# sch.net
KiCad netlist of a schematic drawn in EAGLE
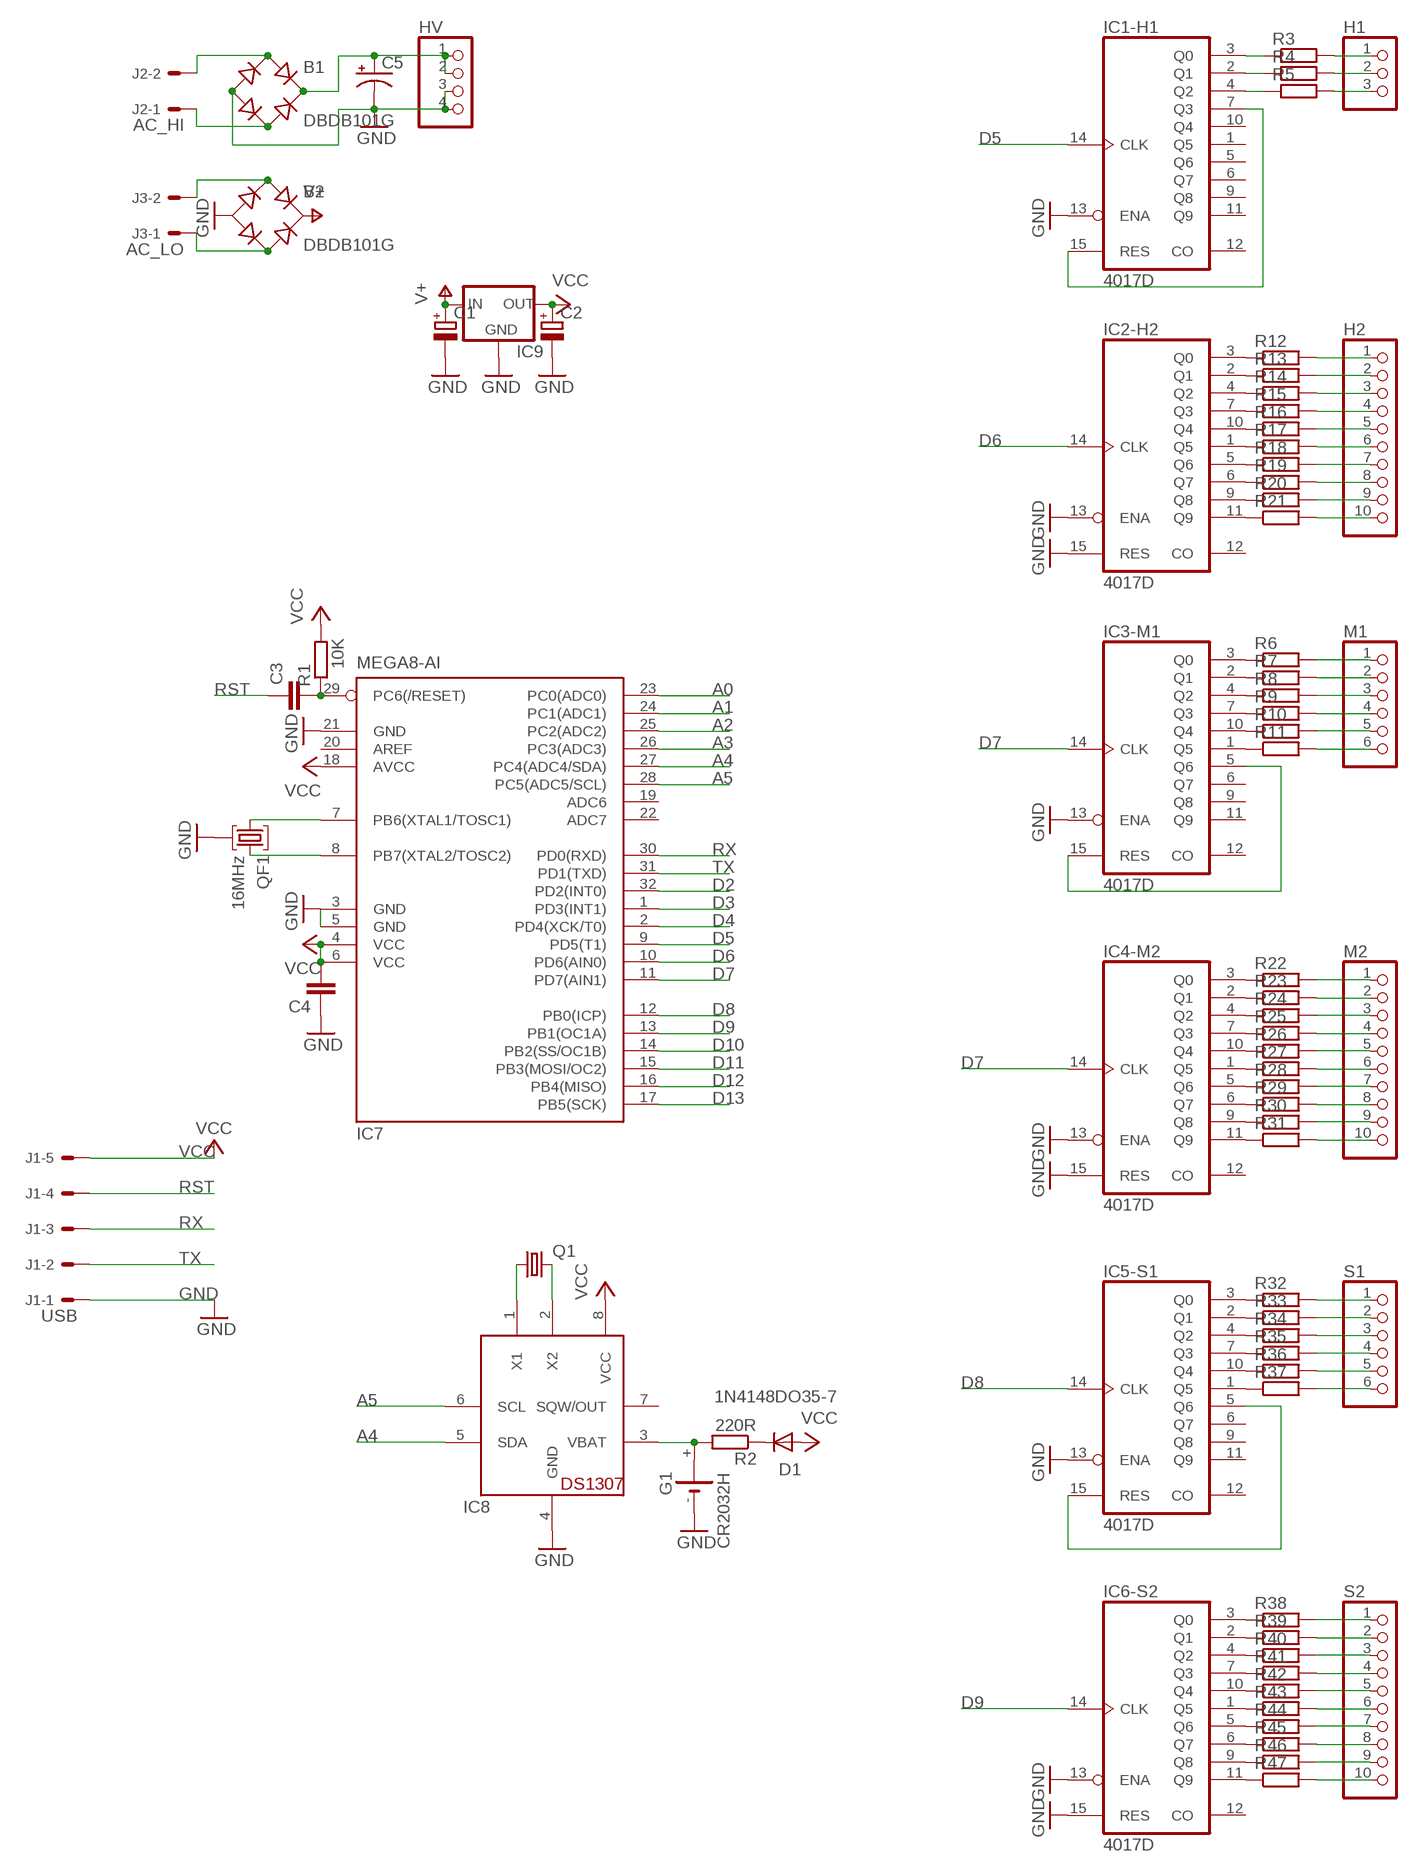
[diagram p0: schematic, sheet 1]

(export (version "E")
  (design (tool "Eeschema 10.0.6"))
  (components
    (comp (ref "B1")
      (value "DBDB101G")
      (footprint "eagle-import:DB")
      (libsource (lib "eagle-import") (part "DB?GDB101"))
    )
    (comp (ref "B2")
      (value "DBDB101G")
      (footprint "eagle-import:DB")
      (libsource (lib "eagle-import") (part "DB?GDB101"))
    )
    (comp (ref "C1")
      (value "CPOL-EU140CLH-1010")
      (footprint "eagle-import:140CLH-1010")
      (libsource (lib "eagle-import") (part "CPOL-EU140CLH-1010"))
    )
    (comp (ref "C2")
      (value "CPOL-EU140CLH-1010")
      (footprint "eagle-import:140CLH-1010")
      (libsource (lib "eagle-import") (part "CPOL-EU140CLH-1010"))
    )
    (comp (ref "C3")
      (value "C-EUC1206K")
      (footprint "eagle-import:C1206K")
      (libsource (lib "eagle-import") (part "C-EUC1206K"))
    )
    (comp (ref "C4")
      (value "C-EUC1206K")
      (footprint "eagle-import:C1206K")
      (libsource (lib "eagle-import") (part "C-EUC1206K"))
    )
    (comp (ref "C5")
      (value "CPOL-USE5-13")
      (footprint "eagle-import:E5-13")
      (libsource (lib "eagle-import") (part "CPOL-USE5-13"))
    )
    (comp (ref "D1")
      (value "1N4148DO35-7")
      (footprint "eagle-import:DO35-7")
      (libsource (lib "eagle-import") (part "1N4148DO35-7"))
    )
    (comp (ref "G1")
      (value "CR2032H")
      (footprint "eagle-import:CR2032H")
      (libsource (lib "eagle-import") (part "CR2032H"))
    )
    (comp (ref "H1")
      (value "PINHD-1X3")
      (footprint "eagle-import:1X03")
      (libsource (lib "eagle-import") (part "PINHD-1X3"))
    )
    (comp (ref "H2")
      (value "PINHD-1X10")
      (footprint "eagle-import:1X10")
      (libsource (lib "eagle-import") (part "PINHD-1X10"))
    )
    (comp (ref "HV")
      (value "PINHD-1X4")
      (footprint "eagle-import:1X04")
      (libsource (lib "eagle-import") (part "PINHD-1X4"))
    )
    (comp (ref "IC1-H1")
      (value "4017D")
      (footprint "eagle-import:SO16")
      (libsource (lib "eagle-import") (part "4017D"))
    )
    (comp (ref "IC2-H2")
      (value "4017D")
      (footprint "eagle-import:SO16")
      (libsource (lib "eagle-import") (part "4017D"))
    )
    (comp (ref "IC3-M1")
      (value "4017D")
      (footprint "eagle-import:SO16")
      (libsource (lib "eagle-import") (part "4017D"))
    )
    (comp (ref "IC4-M2")
      (value "4017D")
      (footprint "eagle-import:SO16")
      (libsource (lib "eagle-import") (part "4017D"))
    )
    (comp (ref "IC5-S1")
      (value "4017D")
      (footprint "eagle-import:SO16")
      (libsource (lib "eagle-import") (part "4017D"))
    )
    (comp (ref "IC6-S2")
      (value "4017D")
      (footprint "eagle-import:SO16")
      (libsource (lib "eagle-import") (part "4017D"))
    )
    (comp (ref "IC7")
      (value "MEGA8-AI")
      (footprint "eagle-import:TQFP32-08")
      (fields (field (name "MPN") "ATMEGA8-16AU"))
      (libsource (lib "eagle-import") (part "MEGA8-AI"))
    )
    (comp (ref "IC8")
      (value "DS1307")
      (footprint "eagle-import:DIL08")
      (libsource (lib "eagle-import") (part "DS1307"))
    )
    (comp (ref "IC9")
      (value "78XXS")
      (footprint "eagle-import:78XXS")
      (libsource (lib "eagle-import") (part "78XXS"))
    )
    (comp (ref "J1")
      (value "USB")
      (footprint "eagle-import:7395-05")
      (libsource (lib "eagle-import") (part "22-?-0505-7058"))
    )
    (comp (ref "J2")
      (value "AC_HI")
      (footprint "eagle-import:7395-02")
      (libsource (lib "eagle-import") (part "22-?-0205-7028"))
    )
    (comp (ref "J3")
      (value "AC_LO")
      (footprint "eagle-import:7395-02")
      (libsource (lib "eagle-import") (part "22-?-0205-7028"))
    )
    (comp (ref "M1")
      (value "PINHD-1X6")
      (footprint "eagle-import:1X06")
      (libsource (lib "eagle-import") (part "PINHD-1X6"))
    )
    (comp (ref "M2")
      (value "PINHD-1X10")
      (footprint "eagle-import:1X10")
      (libsource (lib "eagle-import") (part "PINHD-1X10"))
    )
    (comp (ref "Q1")
      (value "CRYSTALTC26H")
      (footprint "eagle-import:TC26H")
      (libsource (lib "eagle-import") (part "CRYSTALTC26H"))
    )
    (comp (ref "QF1")
      (value "16MHz")
      (footprint "eagle-import:HC49U")
      (libsource (lib "eagle-import") (part "8M10AHC49T"))
    )
    (comp (ref "R1")
      (value "10K")
      (footprint "eagle-import:0207_7")
      (libsource (lib "eagle-import") (part "R-EU_0207/7"))
    )
    (comp (ref "R2")
      (value "220R")
      (footprint "eagle-import:0207_7")
      (libsource (lib "eagle-import") (part "R-EU_0207/7"))
    )
    (comp (ref "R3")
      (value "R-EU_0204/5")
      (footprint "eagle-import:0204_5")
      (libsource (lib "eagle-import") (part "R-EU_0204/5"))
    )
    (comp (ref "R4")
      (value "R-EU_0204/5")
      (footprint "eagle-import:0204_5")
      (libsource (lib "eagle-import") (part "R-EU_0204/5"))
    )
    (comp (ref "R5")
      (value "R-EU_0204/5")
      (footprint "eagle-import:0204_5")
      (libsource (lib "eagle-import") (part "R-EU_0204/5"))
    )
    (comp (ref "R6")
      (value "R-EU_0204/5")
      (footprint "eagle-import:0204_5")
      (libsource (lib "eagle-import") (part "R-EU_0204/5"))
    )
    (comp (ref "R7")
      (value "R-EU_0204/5")
      (footprint "eagle-import:0204_5")
      (libsource (lib "eagle-import") (part "R-EU_0204/5"))
    )
    (comp (ref "R8")
      (value "R-EU_0204/5")
      (footprint "eagle-import:0204_5")
      (libsource (lib "eagle-import") (part "R-EU_0204/5"))
    )
    (comp (ref "R9")
      (value "R-EU_0204/5")
      (footprint "eagle-import:0204_5")
      (libsource (lib "eagle-import") (part "R-EU_0204/5"))
    )
    (comp (ref "R10")
      (value "R-EU_0204/5")
      (footprint "eagle-import:0204_5")
      (libsource (lib "eagle-import") (part "R-EU_0204/5"))
    )
    (comp (ref "R11")
      (value "R-EU_0204/5")
      (footprint "eagle-import:0204_5")
      (libsource (lib "eagle-import") (part "R-EU_0204/5"))
    )
    (comp (ref "R12")
      (value "R-EU_0204/5")
      (footprint "eagle-import:0204_5")
      (libsource (lib "eagle-import") (part "R-EU_0204/5"))
    )
    (comp (ref "R13")
      (value "R-EU_0204/5")
      (footprint "eagle-import:0204_5")
      (libsource (lib "eagle-import") (part "R-EU_0204/5"))
    )
    (comp (ref "R14")
      (value "R-EU_0204/5")
      (footprint "eagle-import:0204_5")
      (libsource (lib "eagle-import") (part "R-EU_0204/5"))
    )
    (comp (ref "R15")
      (value "R-EU_0204/5")
      (footprint "eagle-import:0204_5")
      (libsource (lib "eagle-import") (part "R-EU_0204/5"))
    )
    (comp (ref "R16")
      (value "R-EU_0204/5")
      (footprint "eagle-import:0204_5")
      (libsource (lib "eagle-import") (part "R-EU_0204/5"))
    )
    (comp (ref "R17")
      (value "R-EU_0204/5")
      (footprint "eagle-import:0204_5")
      (libsource (lib "eagle-import") (part "R-EU_0204/5"))
    )
    (comp (ref "R18")
      (value "R-EU_0204/5")
      (footprint "eagle-import:0204_5")
      (libsource (lib "eagle-import") (part "R-EU_0204/5"))
    )
    (comp (ref "R19")
      (value "R-EU_0204/5")
      (footprint "eagle-import:0204_5")
      (libsource (lib "eagle-import") (part "R-EU_0204/5"))
    )
    (comp (ref "R20")
      (value "R-EU_0204/5")
      (footprint "eagle-import:0204_5")
      (libsource (lib "eagle-import") (part "R-EU_0204/5"))
    )
    (comp (ref "R21")
      (value "R-EU_0204/5")
      (footprint "eagle-import:0204_5")
      (libsource (lib "eagle-import") (part "R-EU_0204/5"))
    )
    (comp (ref "R22")
      (value "R-EU_0204/5")
      (footprint "eagle-import:0204_5")
      (libsource (lib "eagle-import") (part "R-EU_0204/5"))
    )
    (comp (ref "R23")
      (value "R-EU_0204/5")
      (footprint "eagle-import:0204_5")
      (libsource (lib "eagle-import") (part "R-EU_0204/5"))
    )
    (comp (ref "R24")
      (value "R-EU_0204/5")
      (footprint "eagle-import:0204_5")
      (libsource (lib "eagle-import") (part "R-EU_0204/5"))
    )
    (comp (ref "R25")
      (value "R-EU_0204/5")
      (footprint "eagle-import:0204_5")
      (libsource (lib "eagle-import") (part "R-EU_0204/5"))
    )
    (comp (ref "R26")
      (value "R-EU_0204/5")
      (footprint "eagle-import:0204_5")
      (libsource (lib "eagle-import") (part "R-EU_0204/5"))
    )
    (comp (ref "R27")
      (value "R-EU_0204/5")
      (footprint "eagle-import:0204_5")
      (libsource (lib "eagle-import") (part "R-EU_0204/5"))
    )
    (comp (ref "R28")
      (value "R-EU_0204/5")
      (footprint "eagle-import:0204_5")
      (libsource (lib "eagle-import") (part "R-EU_0204/5"))
    )
    (comp (ref "R29")
      (value "R-EU_0204/5")
      (footprint "eagle-import:0204_5")
      (libsource (lib "eagle-import") (part "R-EU_0204/5"))
    )
    (comp (ref "R30")
      (value "R-EU_0204/5")
      (footprint "eagle-import:0204_5")
      (libsource (lib "eagle-import") (part "R-EU_0204/5"))
    )
    (comp (ref "R31")
      (value "R-EU_0204/5")
      (footprint "eagle-import:0204_5")
      (libsource (lib "eagle-import") (part "R-EU_0204/5"))
    )
    (comp (ref "R32")
      (value "R-EU_0204/5")
      (footprint "eagle-import:0204_5")
      (libsource (lib "eagle-import") (part "R-EU_0204/5"))
    )
    (comp (ref "R33")
      (value "R-EU_0204/5")
      (footprint "eagle-import:0204_5")
      (libsource (lib "eagle-import") (part "R-EU_0204/5"))
    )
    (comp (ref "R34")
      (value "R-EU_0204/5")
      (footprint "eagle-import:0204_5")
      (libsource (lib "eagle-import") (part "R-EU_0204/5"))
    )
    (comp (ref "R35")
      (value "R-EU_0204/5")
      (footprint "eagle-import:0204_5")
      (libsource (lib "eagle-import") (part "R-EU_0204/5"))
    )
    (comp (ref "R36")
      (value "R-EU_0204/5")
      (footprint "eagle-import:0204_5")
      (libsource (lib "eagle-import") (part "R-EU_0204/5"))
    )
    (comp (ref "R37")
      (value "R-EU_0204/5")
      (footprint "eagle-import:0204_5")
      (libsource (lib "eagle-import") (part "R-EU_0204/5"))
    )
    (comp (ref "R38")
      (value "R-EU_0204/5")
      (footprint "eagle-import:0204_5")
      (libsource (lib "eagle-import") (part "R-EU_0204/5"))
    )
    (comp (ref "R39")
      (value "R-EU_0204/5")
      (footprint "eagle-import:0204_5")
      (libsource (lib "eagle-import") (part "R-EU_0204/5"))
    )
    (comp (ref "R40")
      (value "R-EU_0204/5")
      (footprint "eagle-import:0204_5")
      (libsource (lib "eagle-import") (part "R-EU_0204/5"))
    )
    (comp (ref "R41")
      (value "R-EU_0204/5")
      (footprint "eagle-import:0204_5")
      (libsource (lib "eagle-import") (part "R-EU_0204/5"))
    )
    (comp (ref "R42")
      (value "R-EU_0204/5")
      (footprint "eagle-import:0204_5")
      (libsource (lib "eagle-import") (part "R-EU_0204/5"))
    )
    (comp (ref "R43")
      (value "R-EU_0204/5")
      (footprint "eagle-import:0204_5")
      (libsource (lib "eagle-import") (part "R-EU_0204/5"))
    )
    (comp (ref "R44")
      (value "R-EU_0204/5")
      (footprint "eagle-import:0204_5")
      (libsource (lib "eagle-import") (part "R-EU_0204/5"))
    )
    (comp (ref "R45")
      (value "R-EU_0204/5")
      (footprint "eagle-import:0204_5")
      (libsource (lib "eagle-import") (part "R-EU_0204/5"))
    )
    (comp (ref "R46")
      (value "R-EU_0204/5")
      (footprint "eagle-import:0204_5")
      (libsource (lib "eagle-import") (part "R-EU_0204/5"))
    )
    (comp (ref "R47")
      (value "R-EU_0204/5")
      (footprint "eagle-import:0204_5")
      (libsource (lib "eagle-import") (part "R-EU_0204/5"))
    )
    (comp (ref "S1")
      (value "PINHD-1X6")
      (footprint "eagle-import:1X06")
      (libsource (lib "eagle-import") (part "PINHD-1X6"))
    )
    (comp (ref "S2")
      (value "PINHD-1X10")
      (footprint "eagle-import:1X10")
      (libsource (lib "eagle-import") (part "PINHD-1X10"))
    )
  )
  (nets
    (net (code "1") (name "/A0") (class "Default")
      (node (ref "IC7") (pin "23") (pinfunction "PC0(ADC0)_23") (pintype "bidirectional"))
    )
    (net (code "2") (name "/A1") (class "Default")
      (node (ref "IC7") (pin "24") (pinfunction "PC1(ADC1)_24") (pintype "bidirectional"))
    )
    (net (code "3") (name "/A2") (class "Default")
      (node (ref "IC7") (pin "25") (pinfunction "PC2(ADC2)_25") (pintype "bidirectional"))
    )
    (net (code "4") (name "/A3") (class "Default")
      (node (ref "IC7") (pin "26") (pinfunction "PC3(ADC3)_26") (pintype "bidirectional"))
    )
    (net (code "5") (name "/A4") (class "Default")
      (node (ref "IC7") (pin "27") (pinfunction "PC4(ADC4/SDA)_27") (pintype "bidirectional"))
      (node (ref "IC8") (pin "5") (pinfunction "SDA_5") (pintype "bidirectional"))
    )
    (net (code "6") (name "/A5") (class "Default")
      (node (ref "IC7") (pin "28") (pinfunction "PC5(ADC5/SCL)_28") (pintype "bidirectional"))
      (node (ref "IC8") (pin "6") (pinfunction "SCL_6") (pintype "bidirectional"))
    )
    (net (code "7") (name "/D2") (class "Default")
      (node (ref "IC7") (pin "32") (pinfunction "PD2(INT0)_32") (pintype "bidirectional"))
    )
    (net (code "8") (name "/D3") (class "Default")
      (node (ref "IC7") (pin "1") (pinfunction "PD3(INT1)_1") (pintype "bidirectional"))
    )
    (net (code "9") (name "/D4") (class "Default")
      (node (ref "IC7") (pin "2") (pinfunction "PD4(XCK/T0)_2") (pintype "bidirectional"))
    )
    (net (code "10") (name "/D5") (class "Default")
      (node (ref "IC1-H1") (pin "14") (pinfunction "CLK_14") (pintype "input"))
      (node (ref "IC7") (pin "9") (pinfunction "PD5(T1)_9") (pintype "bidirectional"))
    )
    (net (code "11") (name "/D6") (class "Default")
      (node (ref "IC2-H2") (pin "14") (pinfunction "CLK_14") (pintype "input"))
      (node (ref "IC7") (pin "10") (pinfunction "PD6(AIN0)_10") (pintype "bidirectional"))
    )
    (net (code "12") (name "/D7") (class "Default")
      (node (ref "IC3-M1") (pin "14") (pinfunction "CLK_14") (pintype "input"))
      (node (ref "IC4-M2") (pin "14") (pinfunction "CLK_14") (pintype "input"))
      (node (ref "IC7") (pin "11") (pinfunction "PD7(AIN1)_11") (pintype "bidirectional"))
    )
    (net (code "13") (name "/D8") (class "Default")
      (node (ref "IC5-S1") (pin "14") (pinfunction "CLK_14") (pintype "input"))
      (node (ref "IC7") (pin "12") (pinfunction "PB0(ICP)_12") (pintype "bidirectional"))
    )
    (net (code "14") (name "/D9") (class "Default")
      (node (ref "IC6-S2") (pin "14") (pinfunction "CLK_14") (pintype "input"))
      (node (ref "IC7") (pin "13") (pinfunction "PB1(OC1A)_13") (pintype "bidirectional"))
    )
    (net (code "15") (name "/D10") (class "Default")
      (node (ref "IC7") (pin "14") (pinfunction "PB2(SS/OC1B)_14") (pintype "bidirectional"))
    )
    (net (code "16") (name "/D11") (class "Default")
      (node (ref "IC7") (pin "15") (pinfunction "PB3(MOSI/OC2)_15") (pintype "bidirectional"))
    )
    (net (code "17") (name "/D12") (class "Default")
      (node (ref "IC7") (pin "16") (pinfunction "PB4(MISO)_16") (pintype "bidirectional"))
    )
    (net (code "18") (name "/D13") (class "Default")
      (node (ref "IC7") (pin "17") (pinfunction "PB5(SCK)_17") (pintype "bidirectional"))
    )
    (net (code "19") (name "/RST") (class "Default")
      (node (ref "C3") (pin "1") (pinfunction "1_1") (pintype "passive"))
      (node (ref "J1") (pin "4") (pinfunction "S_4") (pintype "passive"))
    )
    (net (code "20") (name "/RX") (class "Default")
      (node (ref "IC7") (pin "30") (pinfunction "PD0(RXD)_30") (pintype "bidirectional"))
      (node (ref "J1") (pin "3") (pinfunction "S_3") (pintype "passive"))
    )
    (net (code "21") (name "/TX") (class "Default")
      (node (ref "IC7") (pin "31") (pinfunction "PD1(TXD)_31") (pintype "bidirectional"))
      (node (ref "J1") (pin "2") (pinfunction "S_2") (pintype "passive"))
    )
    (net (code "22") (name "GND") (class "Default")
      (node (ref "B1") (pin "-") (pinfunction "-_-") (pintype "passive"))
      (node (ref "B2") (pin "-") (pinfunction "-_-") (pintype "passive"))
      (node (ref "C1") (pin "-") (pinfunction "-_-") (pintype "passive"))
      (node (ref "C2") (pin "-") (pinfunction "-_-") (pintype "passive"))
      (node (ref "C4") (pin "1") (pinfunction "1_1") (pintype "passive"))
      (node (ref "C5") (pin "-") (pinfunction "-_-") (pintype "passive"))
      (node (ref "G1") (pin "-") (pinfunction "-_-") (pintype "passive"))
      (node (ref "HV") (pin "3") (pinfunction "3_3") (pintype "passive"))
      (node (ref "HV") (pin "4") (pinfunction "4_4") (pintype "passive"))
      (node (ref "IC1-H1") (pin "13") (pinfunction "ENA_13") (pintype "input"))
      (node (ref "IC2-H2") (pin "13") (pinfunction "ENA_13") (pintype "input"))
      (node (ref "IC2-H2") (pin "15") (pinfunction "RES_15") (pintype "input"))
      (node (ref "IC3-M1") (pin "13") (pinfunction "ENA_13") (pintype "input"))
      (node (ref "IC4-M2") (pin "13") (pinfunction "ENA_13") (pintype "input"))
      (node (ref "IC4-M2") (pin "15") (pinfunction "RES_15") (pintype "input"))
      (node (ref "IC5-S1") (pin "13") (pinfunction "ENA_13") (pintype "input"))
      (node (ref "IC6-S2") (pin "13") (pinfunction "ENA_13") (pintype "input"))
      (node (ref "IC6-S2") (pin "15") (pinfunction "RES_15") (pintype "input"))
      (node (ref "IC7") (pin "21") (pinfunction "GND_21") (pintype "power_in"))
      (node (ref "IC7") (pin "3") (pinfunction "GND_3") (pintype "power_in"))
      (node (ref "IC7") (pin "5") (pinfunction "GND_5") (pintype "power_in"))
      (node (ref "IC8") (pin "4") (pinfunction "GND_4") (pintype "power_in"))
      (node (ref "IC9") (pin "GND") (pinfunction "GND_GND") (pintype "input"))
      (node (ref "J1") (pin "1") (pinfunction "S_1") (pintype "passive"))
      (node (ref "QF1") (pin "2") (pinfunction "2_2") (pintype "passive"))
    )
    (net (code "23") (name "Net-(B1-Pad+)") (class "Default")
      (node (ref "B1") (pin "+") (pinfunction "+_+") (pintype "passive"))
      (node (ref "C5") (pin "+") (pinfunction "+_+") (pintype "passive"))
      (node (ref "HV") (pin "1") (pinfunction "1_1") (pintype "passive"))
      (node (ref "HV") (pin "2") (pinfunction "2_2") (pintype "passive"))
    )
    (net (code "24") (name "Net-(D1-PadC)") (class "Default")
      (node (ref "D1") (pin "C") (pinfunction "C_C") (pintype "passive"))
      (node (ref "R2") (pin "1") (pinfunction "1_1") (pintype "passive"))
    )
    (net (code "25") (name "Net-(H1-Pad1)") (class "Default")
      (node (ref "H1") (pin "1") (pinfunction "1_1") (pintype "passive"))
      (node (ref "R3") (pin "2") (pinfunction "2_2") (pintype "passive"))
    )
    (net (code "26") (name "Net-(H1-Pad2)") (class "Default")
      (node (ref "H1") (pin "2") (pinfunction "2_2") (pintype "passive"))
      (node (ref "R4") (pin "2") (pinfunction "2_2") (pintype "passive"))
    )
    (net (code "27") (name "Net-(H1-Pad3)") (class "Default")
      (node (ref "H1") (pin "3") (pinfunction "3_3") (pintype "passive"))
      (node (ref "R5") (pin "2") (pinfunction "2_2") (pintype "passive"))
    )
    (net (code "28") (name "Net-(H2-Pad1)") (class "Default")
      (node (ref "H2") (pin "1") (pinfunction "1_1") (pintype "passive"))
      (node (ref "R12") (pin "2") (pinfunction "2_2") (pintype "passive"))
    )
    (net (code "29") (name "Net-(H2-Pad2)") (class "Default")
      (node (ref "H2") (pin "2") (pinfunction "2_2") (pintype "passive"))
      (node (ref "R13") (pin "2") (pinfunction "2_2") (pintype "passive"))
    )
    (net (code "30") (name "Net-(H2-Pad3)") (class "Default")
      (node (ref "H2") (pin "3") (pinfunction "3_3") (pintype "passive"))
      (node (ref "R14") (pin "2") (pinfunction "2_2") (pintype "passive"))
    )
    (net (code "31") (name "Net-(H2-Pad4)") (class "Default")
      (node (ref "H2") (pin "4") (pinfunction "4_4") (pintype "passive"))
      (node (ref "R15") (pin "2") (pinfunction "2_2") (pintype "passive"))
    )
    (net (code "32") (name "Net-(H2-Pad5)") (class "Default")
      (node (ref "H2") (pin "5") (pinfunction "5_5") (pintype "passive"))
      (node (ref "R16") (pin "2") (pinfunction "2_2") (pintype "passive"))
    )
    (net (code "33") (name "Net-(H2-Pad6)") (class "Default")
      (node (ref "H2") (pin "6") (pinfunction "6_6") (pintype "passive"))
      (node (ref "R17") (pin "2") (pinfunction "2_2") (pintype "passive"))
    )
    (net (code "34") (name "Net-(H2-Pad7)") (class "Default")
      (node (ref "H2") (pin "7") (pinfunction "7_7") (pintype "passive"))
      (node (ref "R18") (pin "2") (pinfunction "2_2") (pintype "passive"))
    )
    (net (code "35") (name "Net-(H2-Pad8)") (class "Default")
      (node (ref "H2") (pin "8") (pinfunction "8_8") (pintype "passive"))
      (node (ref "R19") (pin "2") (pinfunction "2_2") (pintype "passive"))
    )
    (net (code "36") (name "Net-(H2-Pad9)") (class "Default")
      (node (ref "H2") (pin "9") (pinfunction "9_9") (pintype "passive"))
      (node (ref "R20") (pin "2") (pinfunction "2_2") (pintype "passive"))
    )
    (net (code "37") (name "Net-(H2-Pad10)") (class "Default")
      (node (ref "H2") (pin "10") (pinfunction "10_10") (pintype "passive"))
      (node (ref "R21") (pin "2") (pinfunction "2_2") (pintype "passive"))
    )
    (net (code "38") (name "Net-(IC1-H1A-Q0)") (class "Default")
      (node (ref "IC1-H1") (pin "3") (pinfunction "Q0_3") (pintype "output"))
      (node (ref "R3") (pin "1") (pinfunction "1_1") (pintype "passive"))
    )
    (net (code "39") (name "Net-(IC1-H1A-Q1)") (class "Default")
      (node (ref "IC1-H1") (pin "2") (pinfunction "Q1_2") (pintype "output"))
      (node (ref "R4") (pin "1") (pinfunction "1_1") (pintype "passive"))
    )
    (net (code "40") (name "Net-(IC1-H1A-Q2)") (class "Default")
      (node (ref "IC1-H1") (pin "4") (pinfunction "Q2_4") (pintype "output"))
      (node (ref "R5") (pin "1") (pinfunction "1_1") (pintype "passive"))
    )
    (net (code "41") (name "Net-(IC1-H1A-Q3)") (class "Default")
      (node (ref "IC1-H1") (pin "15") (pinfunction "RES_15") (pintype "input"))
      (node (ref "IC1-H1") (pin "7") (pinfunction "Q3_7") (pintype "output"))
    )
    (net (code "42") (name "Net-(IC2-H2A-Q0)") (class "Default")
      (node (ref "IC2-H2") (pin "3") (pinfunction "Q0_3") (pintype "output"))
      (node (ref "R12") (pin "1") (pinfunction "1_1") (pintype "passive"))
    )
    (net (code "43") (name "Net-(IC2-H2A-Q1)") (class "Default")
      (node (ref "IC2-H2") (pin "2") (pinfunction "Q1_2") (pintype "output"))
      (node (ref "R13") (pin "1") (pinfunction "1_1") (pintype "passive"))
    )
    (net (code "44") (name "Net-(IC2-H2A-Q2)") (class "Default")
      (node (ref "IC2-H2") (pin "4") (pinfunction "Q2_4") (pintype "output"))
      (node (ref "R14") (pin "1") (pinfunction "1_1") (pintype "passive"))
    )
    (net (code "45") (name "Net-(IC2-H2A-Q3)") (class "Default")
      (node (ref "IC2-H2") (pin "7") (pinfunction "Q3_7") (pintype "output"))
      (node (ref "R15") (pin "1") (pinfunction "1_1") (pintype "passive"))
    )
    (net (code "46") (name "Net-(IC2-H2A-Q4)") (class "Default")
      (node (ref "IC2-H2") (pin "10") (pinfunction "Q4_10") (pintype "output"))
      (node (ref "R16") (pin "1") (pinfunction "1_1") (pintype "passive"))
    )
    (net (code "47") (name "Net-(IC2-H2A-Q5)") (class "Default")
      (node (ref "IC2-H2") (pin "1") (pinfunction "Q5_1") (pintype "output"))
      (node (ref "R17") (pin "1") (pinfunction "1_1") (pintype "passive"))
    )
    (net (code "48") (name "Net-(IC2-H2A-Q6)") (class "Default")
      (node (ref "IC2-H2") (pin "5") (pinfunction "Q6_5") (pintype "output"))
      (node (ref "R18") (pin "1") (pinfunction "1_1") (pintype "passive"))
    )
    (net (code "49") (name "Net-(IC2-H2A-Q7)") (class "Default")
      (node (ref "IC2-H2") (pin "6") (pinfunction "Q7_6") (pintype "output"))
      (node (ref "R19") (pin "1") (pinfunction "1_1") (pintype "passive"))
    )
    (net (code "50") (name "Net-(IC2-H2A-Q8)") (class "Default")
      (node (ref "IC2-H2") (pin "9") (pinfunction "Q8_9") (pintype "output"))
      (node (ref "R20") (pin "1") (pinfunction "1_1") (pintype "passive"))
    )
    (net (code "51") (name "Net-(IC2-H2A-Q9)") (class "Default")
      (node (ref "IC2-H2") (pin "11") (pinfunction "Q9_11") (pintype "output"))
      (node (ref "R21") (pin "1") (pinfunction "1_1") (pintype "passive"))
    )
    (net (code "52") (name "Net-(IC3-M1A-Q0)") (class "Default")
      (node (ref "IC3-M1") (pin "3") (pinfunction "Q0_3") (pintype "output"))
      (node (ref "R6") (pin "1") (pinfunction "1_1") (pintype "passive"))
    )
    (net (code "53") (name "Net-(IC3-M1A-Q1)") (class "Default")
      (node (ref "IC3-M1") (pin "2") (pinfunction "Q1_2") (pintype "output"))
      (node (ref "R7") (pin "1") (pinfunction "1_1") (pintype "passive"))
    )
    (net (code "54") (name "Net-(IC3-M1A-Q2)") (class "Default")
      (node (ref "IC3-M1") (pin "4") (pinfunction "Q2_4") (pintype "output"))
      (node (ref "R8") (pin "1") (pinfunction "1_1") (pintype "passive"))
    )
    (net (code "55") (name "Net-(IC3-M1A-Q3)") (class "Default")
      (node (ref "IC3-M1") (pin "7") (pinfunction "Q3_7") (pintype "output"))
      (node (ref "R9") (pin "1") (pinfunction "1_1") (pintype "passive"))
    )
    (net (code "56") (name "Net-(IC3-M1A-Q4)") (class "Default")
      (node (ref "IC3-M1") (pin "10") (pinfunction "Q4_10") (pintype "output"))
      (node (ref "R10") (pin "1") (pinfunction "1_1") (pintype "passive"))
    )
    (net (code "57") (name "Net-(IC3-M1A-Q5)") (class "Default")
      (node (ref "IC3-M1") (pin "1") (pinfunction "Q5_1") (pintype "output"))
      (node (ref "R11") (pin "1") (pinfunction "1_1") (pintype "passive"))
    )
    (net (code "58") (name "Net-(IC3-M1A-Q6)") (class "Default")
      (node (ref "IC3-M1") (pin "15") (pinfunction "RES_15") (pintype "input"))
      (node (ref "IC3-M1") (pin "5") (pinfunction "Q6_5") (pintype "output"))
    )
    (net (code "59") (name "Net-(IC4-M2A-Q0)") (class "Default")
      (node (ref "IC4-M2") (pin "3") (pinfunction "Q0_3") (pintype "output"))
      (node (ref "R22") (pin "1") (pinfunction "1_1") (pintype "passive"))
    )
    (net (code "60") (name "Net-(IC4-M2A-Q1)") (class "Default")
      (node (ref "IC4-M2") (pin "2") (pinfunction "Q1_2") (pintype "output"))
      (node (ref "R23") (pin "1") (pinfunction "1_1") (pintype "passive"))
    )
    (net (code "61") (name "Net-(IC4-M2A-Q2)") (class "Default")
      (node (ref "IC4-M2") (pin "4") (pinfunction "Q2_4") (pintype "output"))
      (node (ref "R24") (pin "1") (pinfunction "1_1") (pintype "passive"))
    )
    (net (code "62") (name "Net-(IC4-M2A-Q3)") (class "Default")
      (node (ref "IC4-M2") (pin "7") (pinfunction "Q3_7") (pintype "output"))
      (node (ref "R25") (pin "1") (pinfunction "1_1") (pintype "passive"))
    )
    (net (code "63") (name "Net-(IC4-M2A-Q4)") (class "Default")
      (node (ref "IC4-M2") (pin "10") (pinfunction "Q4_10") (pintype "output"))
      (node (ref "R26") (pin "1") (pinfunction "1_1") (pintype "passive"))
    )
    (net (code "64") (name "Net-(IC4-M2A-Q5)") (class "Default")
      (node (ref "IC4-M2") (pin "1") (pinfunction "Q5_1") (pintype "output"))
      (node (ref "R27") (pin "1") (pinfunction "1_1") (pintype "passive"))
    )
    (net (code "65") (name "Net-(IC4-M2A-Q6)") (class "Default")
      (node (ref "IC4-M2") (pin "5") (pinfunction "Q6_5") (pintype "output"))
      (node (ref "R28") (pin "1") (pinfunction "1_1") (pintype "passive"))
    )
    (net (code "66") (name "Net-(IC4-M2A-Q7)") (class "Default")
      (node (ref "IC4-M2") (pin "6") (pinfunction "Q7_6") (pintype "output"))
      (node (ref "R29") (pin "1") (pinfunction "1_1") (pintype "passive"))
    )
    (net (code "67") (name "Net-(IC4-M2A-Q8)") (class "Default")
      (node (ref "IC4-M2") (pin "9") (pinfunction "Q8_9") (pintype "output"))
      (node (ref "R30") (pin "1") (pinfunction "1_1") (pintype "passive"))
    )
    (net (code "68") (name "Net-(IC4-M2A-Q9)") (class "Default")
      (node (ref "IC4-M2") (pin "11") (pinfunction "Q9_11") (pintype "output"))
      (node (ref "R31") (pin "1") (pinfunction "1_1") (pintype "passive"))
    )
    (net (code "69") (name "Net-(IC5-S1A-Q0)") (class "Default")
      (node (ref "IC5-S1") (pin "3") (pinfunction "Q0_3") (pintype "output"))
      (node (ref "R32") (pin "1") (pinfunction "1_1") (pintype "passive"))
    )
    (net (code "70") (name "Net-(IC5-S1A-Q1)") (class "Default")
      (node (ref "IC5-S1") (pin "2") (pinfunction "Q1_2") (pintype "output"))
      (node (ref "R33") (pin "1") (pinfunction "1_1") (pintype "passive"))
    )
    (net (code "71") (name "Net-(IC5-S1A-Q2)") (class "Default")
      (node (ref "IC5-S1") (pin "4") (pinfunction "Q2_4") (pintype "output"))
      (node (ref "R34") (pin "1") (pinfunction "1_1") (pintype "passive"))
    )
    (net (code "72") (name "Net-(IC5-S1A-Q3)") (class "Default")
      (node (ref "IC5-S1") (pin "7") (pinfunction "Q3_7") (pintype "output"))
      (node (ref "R35") (pin "1") (pinfunction "1_1") (pintype "passive"))
    )
    (net (code "73") (name "Net-(IC5-S1A-Q4)") (class "Default")
      (node (ref "IC5-S1") (pin "10") (pinfunction "Q4_10") (pintype "output"))
      (node (ref "R36") (pin "1") (pinfunction "1_1") (pintype "passive"))
    )
    (net (code "74") (name "Net-(IC5-S1A-Q5)") (class "Default")
      (node (ref "IC5-S1") (pin "1") (pinfunction "Q5_1") (pintype "output"))
      (node (ref "R37") (pin "1") (pinfunction "1_1") (pintype "passive"))
    )
    (net (code "75") (name "Net-(IC5-S1A-Q6)") (class "Default")
      (node (ref "IC5-S1") (pin "15") (pinfunction "RES_15") (pintype "input"))
      (node (ref "IC5-S1") (pin "5") (pinfunction "Q6_5") (pintype "output"))
    )
    (net (code "76") (name "Net-(IC6-S2A-Q0)") (class "Default")
      (node (ref "IC6-S2") (pin "3") (pinfunction "Q0_3") (pintype "output"))
      (node (ref "R38") (pin "1") (pinfunction "1_1") (pintype "passive"))
    )
    (net (code "77") (name "Net-(IC6-S2A-Q1)") (class "Default")
      (node (ref "IC6-S2") (pin "2") (pinfunction "Q1_2") (pintype "output"))
      (node (ref "R39") (pin "1") (pinfunction "1_1") (pintype "passive"))
    )
    (net (code "78") (name "Net-(IC6-S2A-Q2)") (class "Default")
      (node (ref "IC6-S2") (pin "4") (pinfunction "Q2_4") (pintype "output"))
      (node (ref "R40") (pin "1") (pinfunction "1_1") (pintype "passive"))
    )
    (net (code "79") (name "Net-(IC6-S2A-Q3)") (class "Default")
      (node (ref "IC6-S2") (pin "7") (pinfunction "Q3_7") (pintype "output"))
      (node (ref "R41") (pin "1") (pinfunction "1_1") (pintype "passive"))
    )
    (net (code "80") (name "Net-(IC6-S2A-Q4)") (class "Default")
      (node (ref "IC6-S2") (pin "10") (pinfunction "Q4_10") (pintype "output"))
      (node (ref "R42") (pin "1") (pinfunction "1_1") (pintype "passive"))
    )
    (net (code "81") (name "Net-(IC6-S2A-Q5)") (class "Default")
      (node (ref "IC6-S2") (pin "1") (pinfunction "Q5_1") (pintype "output"))
      (node (ref "R43") (pin "1") (pinfunction "1_1") (pintype "passive"))
    )
    (net (code "82") (name "Net-(IC6-S2A-Q6)") (class "Default")
      (node (ref "IC6-S2") (pin "5") (pinfunction "Q6_5") (pintype "output"))
      (node (ref "R44") (pin "1") (pinfunction "1_1") (pintype "passive"))
    )
    (net (code "83") (name "Net-(IC6-S2A-Q7)") (class "Default")
      (node (ref "IC6-S2") (pin "6") (pinfunction "Q7_6") (pintype "output"))
      (node (ref "R45") (pin "1") (pinfunction "1_1") (pintype "passive"))
    )
    (net (code "84") (name "Net-(IC6-S2A-Q8)") (class "Default")
      (node (ref "IC6-S2") (pin "9") (pinfunction "Q8_9") (pintype "output"))
      (node (ref "R46") (pin "1") (pinfunction "1_1") (pintype "passive"))
    )
    (net (code "85") (name "Net-(IC6-S2A-Q9)") (class "Default")
      (node (ref "IC6-S2") (pin "11") (pinfunction "Q9_11") (pintype "output"))
      (node (ref "R47") (pin "1") (pinfunction "1_1") (pintype "passive"))
    )
    (net (code "86") (name "Net-(IC7-PB6(XTAL1{slash}TOSC1))") (class "Default")
      (node (ref "IC7") (pin "7") (pinfunction "PB6(XTAL1/TOSC1)_7") (pintype "bidirectional"))
      (node (ref "QF1") (pin "1") (pinfunction "1_1") (pintype "passive"))
    )
    (net (code "87") (name "Net-(IC7-PB7(XTAL2{slash}TOSC2))") (class "Default")
      (node (ref "IC7") (pin "8") (pinfunction "PB7(XTAL2/TOSC2)_8") (pintype "bidirectional"))
      (node (ref "QF1") (pin "3") (pinfunction "3_3") (pintype "passive"))
    )
    (net (code "88") (name "Net-(IC7-PC6({slash}RESET))") (class "Default")
      (node (ref "C3") (pin "2") (pinfunction "2_2") (pintype "passive"))
      (node (ref "IC7") (pin "29") (pinfunction "PC6(/RESET)_29") (pintype "bidirectional"))
      (node (ref "R1") (pin "1") (pinfunction "1_1") (pintype "passive"))
    )
    (net (code "89") (name "Net-(IC8-VBAT)") (class "Default")
      (node (ref "G1") (pin "+") (pinfunction "+_+") (pintype "passive"))
      (node (ref "IC8") (pin "3") (pinfunction "VBAT_3") (pintype "power_in"))
      (node (ref "R2") (pin "2") (pinfunction "2_2") (pintype "passive"))
    )
    (net (code "90") (name "Net-(IC8-X1)") (class "Default")
      (node (ref "IC8") (pin "1") (pinfunction "X1_1") (pintype "passive"))
      (node (ref "Q1") (pin "1") (pinfunction "1_1") (pintype "passive"))
    )
    (net (code "91") (name "Net-(IC8-X2)") (class "Default")
      (node (ref "IC8") (pin "2") (pinfunction "X2_2") (pintype "passive"))
      (node (ref "Q1") (pin "2") (pinfunction "2_2") (pintype "passive"))
    )
    (net (code "92") (name "Net-(J2A-S)") (class "Default")
      (node (ref "B1") (pin "AC2") (pinfunction "AC2_AC2") (pintype "passive"))
      (node (ref "J2") (pin "1") (pinfunction "S_1") (pintype "passive"))
    )
    (net (code "93") (name "Net-(J2B-S)") (class "Default")
      (node (ref "B1") (pin "AC1") (pinfunction "AC1_AC1") (pintype "passive"))
      (node (ref "J2") (pin "2") (pinfunction "S_2") (pintype "passive"))
    )
    (net (code "94") (name "Net-(J3A-S)") (class "Default")
      (node (ref "B2") (pin "AC2") (pinfunction "AC2_AC2") (pintype "passive"))
      (node (ref "J3") (pin "1") (pinfunction "S_1") (pintype "passive"))
    )
    (net (code "95") (name "Net-(J3B-S)") (class "Default")
      (node (ref "B2") (pin "AC1") (pinfunction "AC1_AC1") (pintype "passive"))
      (node (ref "J3") (pin "2") (pinfunction "S_2") (pintype "passive"))
    )
    (net (code "96") (name "Net-(M1-Pad1)") (class "Default")
      (node (ref "M1") (pin "1") (pinfunction "1_1") (pintype "passive"))
      (node (ref "R6") (pin "2") (pinfunction "2_2") (pintype "passive"))
    )
    (net (code "97") (name "Net-(M1-Pad2)") (class "Default")
      (node (ref "M1") (pin "2") (pinfunction "2_2") (pintype "passive"))
      (node (ref "R7") (pin "2") (pinfunction "2_2") (pintype "passive"))
    )
    (net (code "98") (name "Net-(M1-Pad3)") (class "Default")
      (node (ref "M1") (pin "3") (pinfunction "3_3") (pintype "passive"))
      (node (ref "R8") (pin "2") (pinfunction "2_2") (pintype "passive"))
    )
    (net (code "99") (name "Net-(M1-Pad4)") (class "Default")
      (node (ref "M1") (pin "4") (pinfunction "4_4") (pintype "passive"))
      (node (ref "R9") (pin "2") (pinfunction "2_2") (pintype "passive"))
    )
    (net (code "100") (name "Net-(M1-Pad5)") (class "Default")
      (node (ref "M1") (pin "5") (pinfunction "5_5") (pintype "passive"))
      (node (ref "R10") (pin "2") (pinfunction "2_2") (pintype "passive"))
    )
    (net (code "101") (name "Net-(M1-Pad6)") (class "Default")
      (node (ref "M1") (pin "6") (pinfunction "6_6") (pintype "passive"))
      (node (ref "R11") (pin "2") (pinfunction "2_2") (pintype "passive"))
    )
    (net (code "102") (name "Net-(M2-Pad1)") (class "Default")
      (node (ref "M2") (pin "1") (pinfunction "1_1") (pintype "passive"))
      (node (ref "R22") (pin "2") (pinfunction "2_2") (pintype "passive"))
    )
    (net (code "103") (name "Net-(M2-Pad2)") (class "Default")
      (node (ref "M2") (pin "2") (pinfunction "2_2") (pintype "passive"))
      (node (ref "R23") (pin "2") (pinfunction "2_2") (pintype "passive"))
    )
    (net (code "104") (name "Net-(M2-Pad3)") (class "Default")
      (node (ref "M2") (pin "3") (pinfunction "3_3") (pintype "passive"))
      (node (ref "R24") (pin "2") (pinfunction "2_2") (pintype "passive"))
    )
    (net (code "105") (name "Net-(M2-Pad4)") (class "Default")
      (node (ref "M2") (pin "4") (pinfunction "4_4") (pintype "passive"))
      (node (ref "R25") (pin "2") (pinfunction "2_2") (pintype "passive"))
    )
    (net (code "106") (name "Net-(M2-Pad5)") (class "Default")
      (node (ref "M2") (pin "5") (pinfunction "5_5") (pintype "passive"))
      (node (ref "R26") (pin "2") (pinfunction "2_2") (pintype "passive"))
    )
    (net (code "107") (name "Net-(M2-Pad6)") (class "Default")
      (node (ref "M2") (pin "6") (pinfunction "6_6") (pintype "passive"))
      (node (ref "R27") (pin "2") (pinfunction "2_2") (pintype "passive"))
    )
    (net (code "108") (name "Net-(M2-Pad7)") (class "Default")
      (node (ref "M2") (pin "7") (pinfunction "7_7") (pintype "passive"))
      (node (ref "R28") (pin "2") (pinfunction "2_2") (pintype "passive"))
    )
    (net (code "109") (name "Net-(M2-Pad8)") (class "Default")
      (node (ref "M2") (pin "8") (pinfunction "8_8") (pintype "passive"))
      (node (ref "R29") (pin "2") (pinfunction "2_2") (pintype "passive"))
    )
    (net (code "110") (name "Net-(M2-Pad9)") (class "Default")
      (node (ref "M2") (pin "9") (pinfunction "9_9") (pintype "passive"))
      (node (ref "R30") (pin "2") (pinfunction "2_2") (pintype "passive"))
    )
    (net (code "111") (name "Net-(M2-Pad10)") (class "Default")
      (node (ref "M2") (pin "10") (pinfunction "10_10") (pintype "passive"))
      (node (ref "R31") (pin "2") (pinfunction "2_2") (pintype "passive"))
    )
    (net (code "112") (name "Net-(R32-Pad2)") (class "Default")
      (node (ref "R32") (pin "2") (pinfunction "2_2") (pintype "passive"))
      (node (ref "S1") (pin "1") (pinfunction "1_1") (pintype "passive"))
    )
    (net (code "113") (name "Net-(R33-Pad2)") (class "Default")
      (node (ref "R33") (pin "2") (pinfunction "2_2") (pintype "passive"))
      (node (ref "S1") (pin "2") (pinfunction "2_2") (pintype "passive"))
    )
    (net (code "114") (name "Net-(R34-Pad2)") (class "Default")
      (node (ref "R34") (pin "2") (pinfunction "2_2") (pintype "passive"))
      (node (ref "S1") (pin "3") (pinfunction "3_3") (pintype "passive"))
    )
    (net (code "115") (name "Net-(R35-Pad2)") (class "Default")
      (node (ref "R35") (pin "2") (pinfunction "2_2") (pintype "passive"))
      (node (ref "S1") (pin "4") (pinfunction "4_4") (pintype "passive"))
    )
    (net (code "116") (name "Net-(R36-Pad2)") (class "Default")
      (node (ref "R36") (pin "2") (pinfunction "2_2") (pintype "passive"))
      (node (ref "S1") (pin "5") (pinfunction "5_5") (pintype "passive"))
    )
    (net (code "117") (name "Net-(R37-Pad2)") (class "Default")
      (node (ref "R37") (pin "2") (pinfunction "2_2") (pintype "passive"))
      (node (ref "S1") (pin "6") (pinfunction "6_6") (pintype "passive"))
    )
    (net (code "118") (name "Net-(R38-Pad2)") (class "Default")
      (node (ref "R38") (pin "2") (pinfunction "2_2") (pintype "passive"))
      (node (ref "S2") (pin "1") (pinfunction "1_1") (pintype "passive"))
    )
    (net (code "119") (name "Net-(R39-Pad2)") (class "Default")
      (node (ref "R39") (pin "2") (pinfunction "2_2") (pintype "passive"))
      (node (ref "S2") (pin "2") (pinfunction "2_2") (pintype "passive"))
    )
    (net (code "120") (name "Net-(R40-Pad2)") (class "Default")
      (node (ref "R40") (pin "2") (pinfunction "2_2") (pintype "passive"))
      (node (ref "S2") (pin "3") (pinfunction "3_3") (pintype "passive"))
    )
    (net (code "121") (name "Net-(R41-Pad2)") (class "Default")
      (node (ref "R41") (pin "2") (pinfunction "2_2") (pintype "passive"))
      (node (ref "S2") (pin "4") (pinfunction "4_4") (pintype "passive"))
    )
    (net (code "122") (name "Net-(R42-Pad2)") (class "Default")
      (node (ref "R42") (pin "2") (pinfunction "2_2") (pintype "passive"))
      (node (ref "S2") (pin "5") (pinfunction "5_5") (pintype "passive"))
    )
    (net (code "123") (name "Net-(R43-Pad2)") (class "Default")
      (node (ref "R43") (pin "2") (pinfunction "2_2") (pintype "passive"))
      (node (ref "S2") (pin "6") (pinfunction "6_6") (pintype "passive"))
    )
    (net (code "124") (name "Net-(R44-Pad2)") (class "Default")
      (node (ref "R44") (pin "2") (pinfunction "2_2") (pintype "passive"))
      (node (ref "S2") (pin "7") (pinfunction "7_7") (pintype "passive"))
    )
    (net (code "125") (name "Net-(R45-Pad2)") (class "Default")
      (node (ref "R45") (pin "2") (pinfunction "2_2") (pintype "passive"))
      (node (ref "S2") (pin "8") (pinfunction "8_8") (pintype "passive"))
    )
    (net (code "126") (name "Net-(R46-Pad2)") (class "Default")
      (node (ref "R46") (pin "2") (pinfunction "2_2") (pintype "passive"))
      (node (ref "S2") (pin "9") (pinfunction "9_9") (pintype "passive"))
    )
    (net (code "127") (name "Net-(R47-Pad2)") (class "Default")
      (node (ref "R47") (pin "2") (pinfunction "2_2") (pintype "passive"))
      (node (ref "S2") (pin "10") (pinfunction "10_10") (pintype "passive"))
    )
    (net (code "128") (name "V+") (class "Default")
      (node (ref "B2") (pin "+") (pinfunction "+_+") (pintype "passive"))
      (node (ref "C1") (pin "+") (pinfunction "+_+") (pintype "passive"))
      (node (ref "IC9") (pin "IN") (pinfunction "IN_IN") (pintype "input"))
    )
    (net (code "129") (name "VCC") (class "Default")
      (node (ref "C2") (pin "+") (pinfunction "+_+") (pintype "passive"))
      (node (ref "C4") (pin "2") (pinfunction "2_2") (pintype "passive"))
      (node (ref "D1") (pin "A") (pinfunction "A_A") (pintype "passive"))
      (node (ref "IC7") (pin "18") (pinfunction "AVCC_18") (pintype "power_in"))
      (node (ref "IC7") (pin "4") (pinfunction "VCC_4") (pintype "power_in"))
      (node (ref "IC7") (pin "6") (pinfunction "VCC_6") (pintype "power_in"))
      (node (ref "IC8") (pin "8") (pinfunction "VCC_8") (pintype "power_in"))
      (node (ref "IC9") (pin "OUT") (pinfunction "OUT_OUT") (pintype "passive"))
      (node (ref "J1") (pin "5") (pinfunction "S_5") (pintype "passive"))
      (node (ref "R1") (pin "2") (pinfunction "2_2") (pintype "passive"))
    )
    (net (code "130") (name "unconnected-(G1-+-Pad+@1)") (class "Default")
      (node (ref "G1") (pin "+@1") (pinfunction "+_+@1") (pintype "passive"))
    )
    (net (code "131") (name "unconnected-(IC1-H1A-CO-Pad12)") (class "Default")
      (node (ref "IC1-H1") (pin "12") (pinfunction "CO_12") (pintype "output"))
    )
    (net (code "132") (name "unconnected-(IC1-H1A-Q4-Pad10)") (class "Default")
      (node (ref "IC1-H1") (pin "10") (pinfunction "Q4_10") (pintype "output"))
    )
    (net (code "133") (name "unconnected-(IC1-H1A-Q5-Pad1)") (class "Default")
      (node (ref "IC1-H1") (pin "1") (pinfunction "Q5_1") (pintype "output"))
    )
    (net (code "134") (name "unconnected-(IC1-H1A-Q6-Pad5)") (class "Default")
      (node (ref "IC1-H1") (pin "5") (pinfunction "Q6_5") (pintype "output"))
    )
    (net (code "135") (name "unconnected-(IC1-H1A-Q7-Pad6)") (class "Default")
      (node (ref "IC1-H1") (pin "6") (pinfunction "Q7_6") (pintype "output"))
    )
    (net (code "136") (name "unconnected-(IC1-H1A-Q8-Pad9)") (class "Default")
      (node (ref "IC1-H1") (pin "9") (pinfunction "Q8_9") (pintype "output"))
    )
    (net (code "137") (name "unconnected-(IC1-H1A-Q9-Pad11)") (class "Default")
      (node (ref "IC1-H1") (pin "11") (pinfunction "Q9_11") (pintype "output"))
    )
    (net (code "138") (name "unconnected-(IC2-H2A-CO-Pad12)") (class "Default")
      (node (ref "IC2-H2") (pin "12") (pinfunction "CO_12") (pintype "output"))
    )
    (net (code "139") (name "unconnected-(IC3-M1A-CO-Pad12)") (class "Default")
      (node (ref "IC3-M1") (pin "12") (pinfunction "CO_12") (pintype "output"))
    )
    (net (code "140") (name "unconnected-(IC3-M1A-Q7-Pad6)") (class "Default")
      (node (ref "IC3-M1") (pin "6") (pinfunction "Q7_6") (pintype "output"))
    )
    (net (code "141") (name "unconnected-(IC3-M1A-Q8-Pad9)") (class "Default")
      (node (ref "IC3-M1") (pin "9") (pinfunction "Q8_9") (pintype "output"))
    )
    (net (code "142") (name "unconnected-(IC3-M1A-Q9-Pad11)") (class "Default")
      (node (ref "IC3-M1") (pin "11") (pinfunction "Q9_11") (pintype "output"))
    )
    (net (code "143") (name "unconnected-(IC4-M2A-CO-Pad12)") (class "Default")
      (node (ref "IC4-M2") (pin "12") (pinfunction "CO_12") (pintype "output"))
    )
    (net (code "144") (name "unconnected-(IC5-S1A-CO-Pad12)") (class "Default")
      (node (ref "IC5-S1") (pin "12") (pinfunction "CO_12") (pintype "output"))
    )
    (net (code "145") (name "unconnected-(IC5-S1A-Q7-Pad6)") (class "Default")
      (node (ref "IC5-S1") (pin "6") (pinfunction "Q7_6") (pintype "output"))
    )
    (net (code "146") (name "unconnected-(IC5-S1A-Q8-Pad9)") (class "Default")
      (node (ref "IC5-S1") (pin "9") (pinfunction "Q8_9") (pintype "output"))
    )
    (net (code "147") (name "unconnected-(IC5-S1A-Q9-Pad11)") (class "Default")
      (node (ref "IC5-S1") (pin "11") (pinfunction "Q9_11") (pintype "output"))
    )
    (net (code "148") (name "unconnected-(IC6-S2A-CO-Pad12)") (class "Default")
      (node (ref "IC6-S2") (pin "12") (pinfunction "CO_12") (pintype "output"))
    )
    (net (code "149") (name "unconnected-(IC7-ADC6-Pad19)") (class "Default")
      (node (ref "IC7") (pin "19") (pinfunction "ADC6_19") (pintype "bidirectional"))
    )
    (net (code "150") (name "unconnected-(IC7-ADC7-Pad22)") (class "Default")
      (node (ref "IC7") (pin "22") (pinfunction "ADC7_22") (pintype "bidirectional"))
    )
    (net (code "151") (name "unconnected-(IC7-AREF-Pad20)") (class "Default")
      (node (ref "IC7") (pin "20") (pinfunction "AREF_20") (pintype "passive"))
    )
    (net (code "152") (name "unconnected-(IC8-SQW{slash}OUT-Pad7)") (class "Default")
      (node (ref "IC8") (pin "7") (pinfunction "SQW/OUT_7") (pintype "bidirectional"))
    )
  )
)
